# PR9024.net
KiCad netlist of a schematic drawn in EAGLE
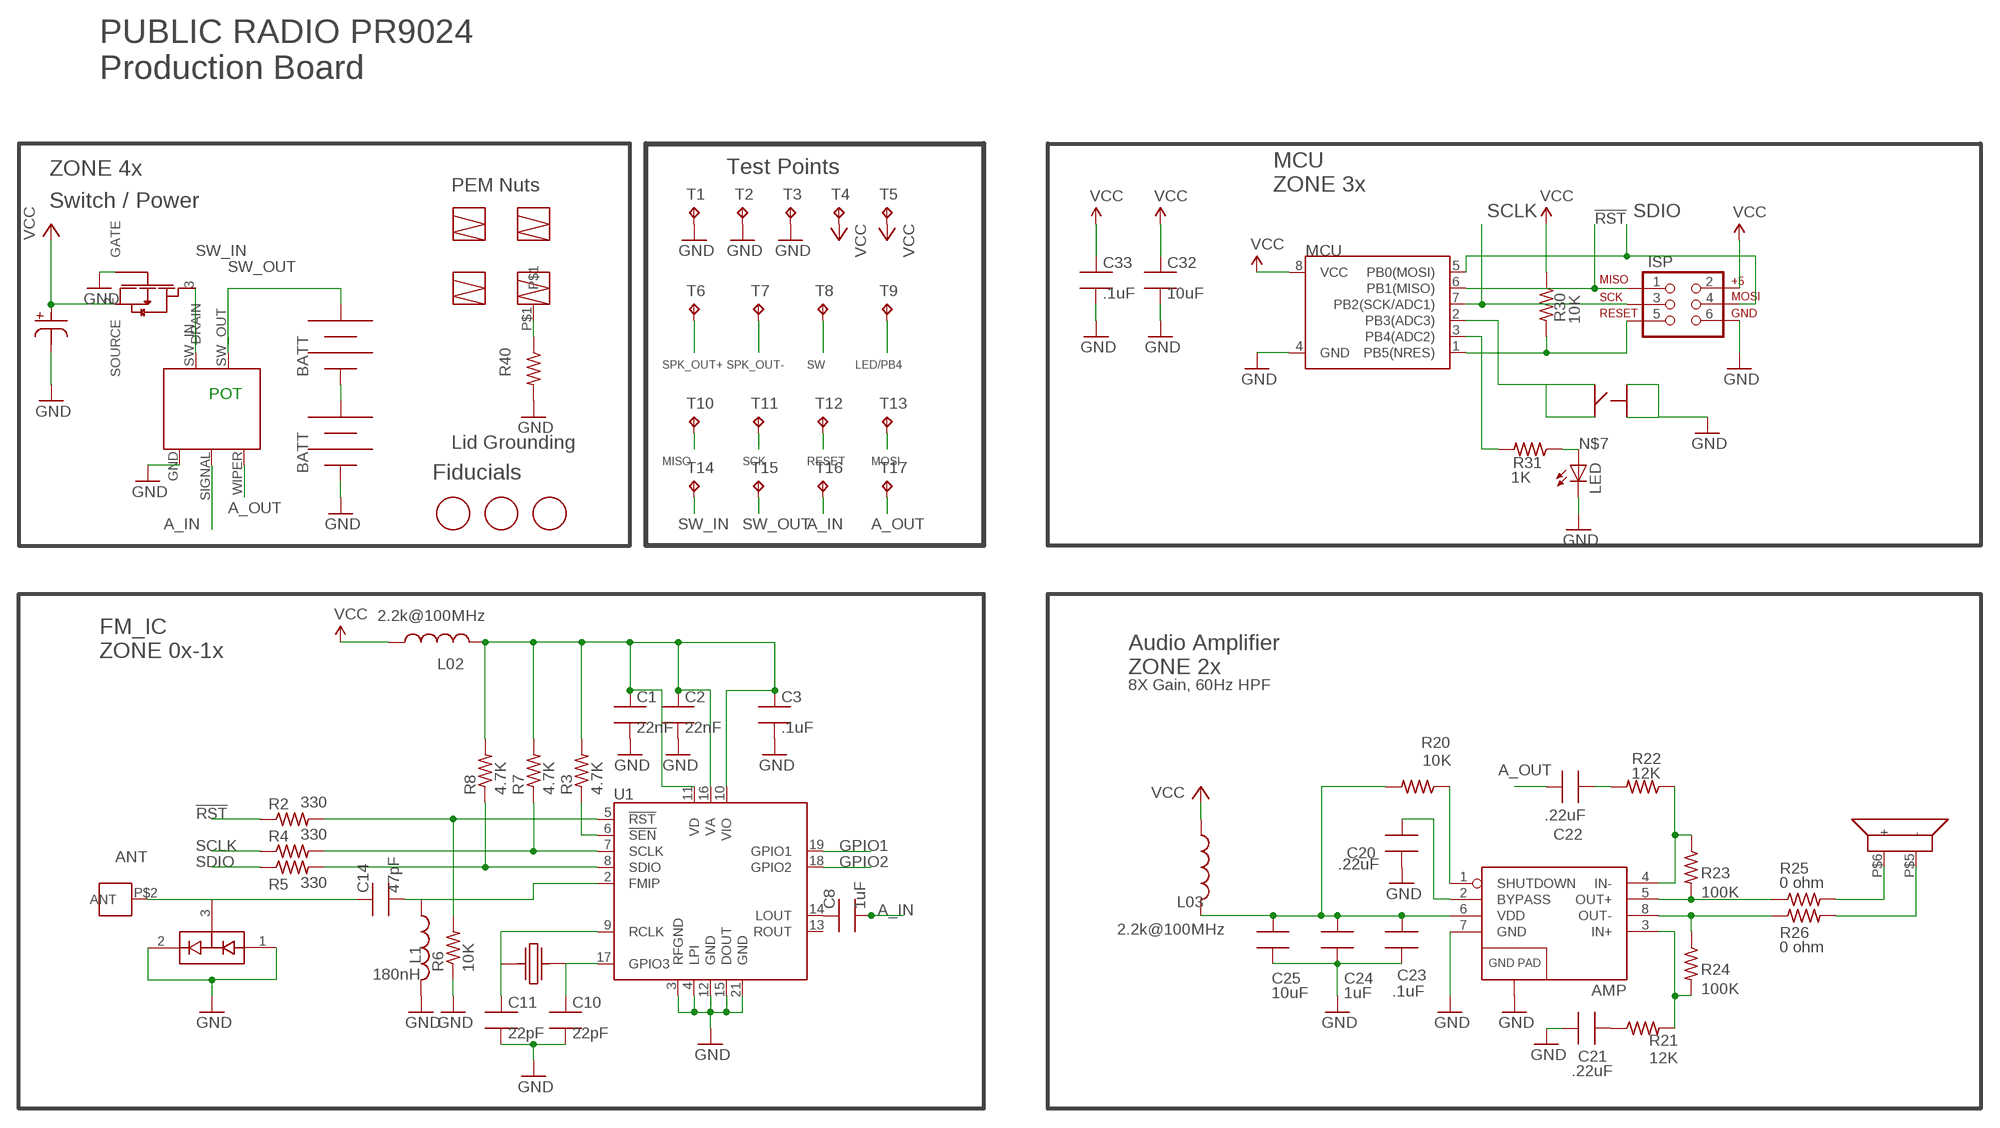
[diagram p0: schematic, sheet 1]

(export (version "E")
  (design (tool "Eeschema 10.0.6"))
  (components
    (comp (ref "AMP")
      (value "TPA6203A1")
      (footprint "eagle-import:8-MSOP")
      (libsource (lib "eagle-import") (part "TPA6203A1"))
    )
    (comp (ref "ANT_MOUNT")
      (value "DNP")
      (footprint "eagle-import:PEM_M3")
      (libsource (lib "eagle-import") (part "M3_PEMNUT"))
    )
    (comp (ref "C1")
      (value "22nF")
      (footprint "eagle-import:0603_CPL")
      (fields
        (field (name "MFG_PN") "CL10B223KB8NNNC")
        (field (name "TOL") "10%")
        (field (name "VOLTAGE") "16V")
      )
      (libsource (lib "eagle-import") (part "C_SMT_0603_CPL"))
    )
    (comp (ref "C2")
      (value "22nF")
      (footprint "eagle-import:0603_CPL")
      (fields
        (field (name "MFG_PN") "CL10B223KB8NNNC")
        (field (name "TOL") "10%")
        (field (name "VOLTAGE") "16V")
      )
      (libsource (lib "eagle-import") (part "C_SMT_0603_CPL"))
    )
    (comp (ref "C3")
      (value ".1uF")
      (footprint "eagle-import:0603_CPL")
      (fields
        (field (name "MFG_PN") "CL10B104KB8SFNC")
        (field (name "TOL") "10%")
        (field (name "VOLTAGE") "16V")
      )
      (libsource (lib "eagle-import") (part "C_SMT_0603_CPL"))
    )
    (comp (ref "C8")
      (value "1uF")
      (footprint "eagle-import:0603_CPL")
      (fields
        (field (name "MFG_PN") "CL10B105KP8NNNC")
        (field (name "TOL") "10%")
        (field (name "VOLTAGE") "10V")
      )
      (libsource (lib "eagle-import") (part "C_SMT_0603_CPL"))
    )
    (comp (ref "C10")
      (value "22pF")
      (footprint "eagle-import:0603_CPL")
      (fields
        (field (name "MFG_PN") "C1608C0G1H220J080AA")
        (field (name "TOL") "5%")
        (field (name "VOLTAGE") "50V")
      )
      (libsource (lib "eagle-import") (part "C_SMT_0603_CPL"))
    )
    (comp (ref "C11")
      (value "22pF")
      (footprint "eagle-import:0603_CPL")
      (fields
        (field (name "MFG_PN") "C1608C0G1H220J080AA")
        (field (name "TOL") "5%")
        (field (name "VOLTAGE") "50V")
      )
      (libsource (lib "eagle-import") (part "C_SMT_0603_CPL"))
    )
    (comp (ref "C14")
      (value "47pF")
      (footprint "eagle-import:0603_CPL")
      (fields
        (field (name "MFG_PN") "CL10C470JB8NCNC")
        (field (name "TOL") "5%")
        (field (name "VOLTAGE") "50V")
      )
      (libsource (lib "eagle-import") (part "C_SMT_0603_CPL"))
    )
    (comp (ref "C20")
      (value ".22uF")
      (footprint "eagle-import:0603_CPL")
      (fields
        (field (name "MFG_PN") "C1608X7R1C224K080AC")
        (field (name "TOL") "10%")
        (field (name "VOLTAGE") "16V")
      )
      (libsource (lib "eagle-import") (part "C_SMT_0603_CPL"))
    )
    (comp (ref "C21")
      (value ".22uF")
      (footprint "eagle-import:0603_CPL")
      (fields
        (field (name "MFG_PN") "C1608X7R1C224K080AC")
        (field (name "TOL") "10%")
        (field (name "VOLTAGE") "16V")
      )
      (libsource (lib "eagle-import") (part "C_SMT_0603_CPL"))
    )
    (comp (ref "C22")
      (value ".22uF")
      (footprint "eagle-import:0603_CPL")
      (fields
        (field (name "MFG_PN") "C1608X7R1C224K080AC")
        (field (name "TOL") "10%")
        (field (name "VOLTAGE") "16V")
      )
      (libsource (lib "eagle-import") (part "C_SMT_0603_CPL"))
    )
    (comp (ref "C23")
      (value ".1uF")
      (footprint "eagle-import:0603_CPL")
      (fields
        (field (name "MFG_PN") "CL10B104KB8SFNC")
        (field (name "TOL") "10%")
        (field (name "VOLTAGE") "16V")
      )
      (libsource (lib "eagle-import") (part "C_SMT_0603_CPL"))
    )
    (comp (ref "C24")
      (value "1uF")
      (footprint "eagle-import:0603_CPL")
      (fields
        (field (name "MFG_PN") "CL10B105KP8NNNC")
        (field (name "TOL") "10%")
        (field (name "VOLTAGE") "10V")
      )
      (libsource (lib "eagle-import") (part "C_SMT_0603_CPL"))
    )
    (comp (ref "C25")
      (value "10uF")
      (footprint "eagle-import:0603_CPL")
      (fields
        (field (name "MFG_PN") "CL10A106MQ8NNNC")
        (field (name "TOL") "20%")
        (field (name "VOLTAGE") "6.3V")
      )
      (libsource (lib "eagle-import") (part "C_SMT_0603_CPL"))
    )
    (comp (ref "C32")
      (value "10uF")
      (footprint "eagle-import:0603_CPL")
      (fields
        (field (name "MFG_PN") "CL10A106MQ8NNNC")
        (field (name "TOL") "20%")
        (field (name "VOLTAGE") "6.3V")
      )
      (libsource (lib "eagle-import") (part "C_SMT_0603_CPL"))
    )
    (comp (ref "C33")
      (value ".1uF")
      (footprint "eagle-import:0603_CPL")
      (fields
        (field (name "MFG_PN") "CL10B104KB8SFNC")
        (field (name "TOL") "10%")
        (field (name "VOLTAGE") "16V")
      )
      (libsource (lib "eagle-import") (part "C_SMT_0603_CPL"))
    )
    (comp (ref "C40")
      (value "220uF")
      (footprint "eagle-import:NICHICON_UD_63")
      (fields (field (name "TOL") "20%") (field (name "VOLTAGE") "16V"))
      (libsource (lib "eagle-import") (part "NICHICON_SERIESUD"))
    )
    (comp (ref "D1")
      (value "BAV99")
      (footprint "eagle-import:SOT23_CPL")
      (fields (field (name "MFG_PN") "BAV99,215"))
      (libsource (lib "eagle-import") (part "BAV99"))
    )
    (comp (ref "FET1")
      (value "AO3435")
      (footprint "eagle-import:SOT23_CPL")
      (fields (field (name "MFG_PN") "AO3435"))
      (libsource (lib "eagle-import") (part "AO3435"))
    )
    (comp (ref "ISP")
      (value "AVR_SPI_PRG_6NS")
      (footprint "eagle-import:2X3-NS")
      (libsource (lib "eagle-import") (part "AVR_SPI_PRG_6NS"))
    )
    (comp (ref "JP5")
      (value "BK-92_MPD_AA_BATT_CLIP")
      (footprint "eagle-import:BK92_AA_BATT")
      (fields (field (name "MFG_PN") "2 of BK92 - supplied by CL Labs"))
      (libsource (lib "eagle-import") (part "BK-92_MPD_AA_BATT_CLIP"))
    )
    (comp (ref "JP6")
      (value "BK-92_MPD_AA_BATT_CLIP")
      (footprint "eagle-import:BK92_AA_BATT")
      (fields (field (name "MFG_PN") "2 of BK92 - supplied by CL Labs"))
      (libsource (lib "eagle-import") (part "BK-92_MPD_AA_BATT_CLIP"))
    )
    (comp (ref "L1")
      (value "180nH")
      (footprint "eagle-import:0805_ADAFRUIT")
      (fields
        (field (name "CURRENT") "400mA")
        (field (name "DCR") "640m")
        (field (name "MFG_PN") "AISC-0805-R18J-T")
        (field (name "TOL") "5%")
      )
      (libsource (lib "eagle-import") (part "L_SMT_0805_ADAFRUIT"))
    )
    (comp (ref "L02")
      (value "2.2k@100MHz")
      (footprint "eagle-import:0603_CPL")
      (fields
        (field (name "CURRENT") "150mA")
        (field (name "DCR") "2.3")
        (field (name "MFG_PN") "HZ0603A222R-10")
      )
      (libsource (lib "eagle-import") (part "L_SMT_0603_CPL"))
    )
    (comp (ref "L03")
      (value "2.2k@100MHz")
      (footprint "eagle-import:0603_CPL")
      (fields
        (field (name "CURRENT") "150mA")
        (field (name "DCR") "2.3")
        (field (name "MFG_PN") "HZ0603A222R-10")
      )
      (libsource (lib "eagle-import") (part "L_SMT_0603_CPL"))
    )
    (comp (ref "LED")
      (value "LEDCHIPLED_0805")
      (footprint "eagle-import:CHIPLED_0805")
      (libsource (lib "eagle-import") (part "LEDCHIPLED_0805"))
    )
    (comp (ref "MARK1")
      (value "FIDUCIAL")
      (footprint "eagle-import:FIDUCIAL_1MM")
      (libsource (lib "eagle-import") (part "FIDUCIAL"))
    )
    (comp (ref "MARK2")
      (value "FIDUCIAL")
      (footprint "eagle-import:FIDUCIAL_1MM")
      (libsource (lib "eagle-import") (part "FIDUCIAL"))
    )
    (comp (ref "MARK3")
      (value "FIDUCIAL")
      (footprint "eagle-import:FIDUCIAL_1MM")
      (libsource (lib "eagle-import") (part "FIDUCIAL"))
    )
    (comp (ref "MCU")
      (value "ATTINY45TINY45-20-SMT")
      (footprint "eagle-import:8-SOIC")
      (libsource (lib "eagle-import") (part "ATTINY45TINY45-20-SMT"))
    )
    (comp (ref "R1")
      (value "VOLUME_POT")
      (footprint "eagle-import:H17112NS_A10K_L20F-002")
      (libsource (lib "eagle-import") (part "VOLUME_POT"))
    )
    (comp (ref "R2")
      (value "330")
      (footprint "eagle-import:0603_CPL")
      (fields (field (name "MFG_PN") "MCR03ERTJ331") (field (name "POWER") "1/10W") (field (name "TOL") "5%"))
      (libsource (lib "eagle-import") (part "R_SMT_R0603_CPL"))
    )
    (comp (ref "R3")
      (value "4.7K")
      (footprint "eagle-import:0603_CPL")
      (fields
        (field (name "MFG_PN") "ERJ-3EKF4701V")
        (field (name "POWER") "1/10W")
        (field (name "TOL") "1%")
      )
      (libsource (lib "eagle-import") (part "R_SMT_R0603_CPL"))
    )
    (comp (ref "R4")
      (value "330")
      (footprint "eagle-import:0603_CPL")
      (fields (field (name "MFG_PN") "MCR03ERTJ331") (field (name "POWER") "1/10W") (field (name "TOL") "5%"))
      (libsource (lib "eagle-import") (part "R_SMT_R0603_CPL"))
    )
    (comp (ref "R5")
      (value "330")
      (footprint "eagle-import:0603_CPL")
      (fields (field (name "MFG_PN") "MCR03ERTJ331") (field (name "POWER") "1/10W") (field (name "TOL") "5%"))
      (libsource (lib "eagle-import") (part "R_SMT_R0603_CPL"))
    )
    (comp (ref "R6")
      (value "10K")
      (footprint "eagle-import:0603_CPL")
      (fields
        (field (name "MFG_PN") "ERJ-3GEYJ103V")
        (field (name "POWER") "1/10W")
        (field (name "TOL") "5%")
      )
      (libsource (lib "eagle-import") (part "R_SMT_R0603_CPL"))
    )
    (comp (ref "R7")
      (value "4.7K")
      (footprint "eagle-import:0603_CPL")
      (fields
        (field (name "MFG_PN") "ERJ-3EKF4701V")
        (field (name "POWER") "1/10W")
        (field (name "TOL") "1%")
      )
      (libsource (lib "eagle-import") (part "R_SMT_R0603_CPL"))
    )
    (comp (ref "R8")
      (value "4.7K")
      (footprint "eagle-import:0603_CPL")
      (fields
        (field (name "MFG_PN") "ERJ-3EKF4701V")
        (field (name "POWER") "1/10W")
        (field (name "TOL") "1%")
      )
      (libsource (lib "eagle-import") (part "R_SMT_R0603_CPL"))
    )
    (comp (ref "R20")
      (value "10K")
      (footprint "eagle-import:0603_CPL")
      (fields
        (field (name "MFG_PN") "ERJ-3GEYJ103V")
        (field (name "POWER") "1/10W")
        (field (name "TOL") "5%")
      )
      (libsource (lib "eagle-import") (part "R_SMT_R0603_CPL"))
    )
    (comp (ref "R21")
      (value "12K")
      (footprint "eagle-import:0603_CPL")
      (fields
        (field (name "MFG_PN") "RC0603FR-0712KL")
        (field (name "POWER") "1/10W")
        (field (name "TOL") "1%")
      )
      (libsource (lib "eagle-import") (part "R_SMT_R0603_CPL"))
    )
    (comp (ref "R22")
      (value "12K")
      (footprint "eagle-import:0603_CPL")
      (fields
        (field (name "MFG_PN") "RC0603FR-0712KL")
        (field (name "POWER") "1/10W")
        (field (name "TOL") "1%")
      )
      (libsource (lib "eagle-import") (part "R_SMT_R0603_CPL"))
    )
    (comp (ref "R23")
      (value "100K")
      (footprint "eagle-import:0603_CPL")
      (fields
        (field (name "MFG_PN") "ERJ-3EKF1003V")
        (field (name "POWER") "1/10W")
        (field (name "TOL") "1%")
      )
      (libsource (lib "eagle-import") (part "R_SMT_R0603_CPL"))
    )
    (comp (ref "R24")
      (value "100K")
      (footprint "eagle-import:0603_CPL")
      (fields
        (field (name "MFG_PN") "ERJ-3EKF1003V")
        (field (name "POWER") "1/10W")
        (field (name "TOL") "1%")
      )
      (libsource (lib "eagle-import") (part "R_SMT_R0603_CPL"))
    )
    (comp (ref "R25")
      (value "0 ohm")
      (footprint "eagle-import:0805_ADAFRUIT")
      (fields (field (name "MFG_PN") "ERJ-6GEY0R00V "))
      (libsource (lib "eagle-import") (part "R_SMT_0805_ADAFRUIT"))
    )
    (comp (ref "R26")
      (value "0 ohm")
      (footprint "eagle-import:0805_ADAFRUIT")
      (fields (field (name "MFG_PN") "ERJ-6GEY0R00V "))
      (libsource (lib "eagle-import") (part "R_SMT_0805_ADAFRUIT"))
    )
    (comp (ref "R30")
      (value "10K")
      (footprint "eagle-import:0603_CPL")
      (fields
        (field (name "MFG_PN") "ERJ-3GEYJ103V")
        (field (name "POWER") "1/10W")
        (field (name "TOL") "5%")
      )
      (libsource (lib "eagle-import") (part "R_SMT_R0603_CPL"))
    )
    (comp (ref "R31")
      (value "1K")
      (footprint "eagle-import:0603_CPL")
      (fields
        (field (name "MFG_PN") "ERJ-3EKF1001V")
        (field (name "POWER") "1/10W")
        (field (name "TOL") "1%")
      )
      (libsource (lib "eagle-import") (part "R_SMT_R0603_CPL"))
    )
    (comp (ref "R40")
      (value "DNP")
      (footprint "eagle-import:0603_CPL")
      (fields (field (name "MFG_PN") "ERJ-3GEY0R00V"))
      (libsource (lib "eagle-import") (part "R_SMT_R0603_CPL"))
    )
    (comp (ref "SPKR_PLACE")
      (value "DNP")
      (footprint "eagle-import:PR2024_SPKR_PLACE(SMD)")
      (libsource (lib "eagle-import") (part "PR2024_SPKR_SMD"))
    )
    (comp (ref "SW1")
      (value "C&K_PTS645")
      (footprint "eagle-import:C&K_PTS645_SMT")
      (libsource (lib "eagle-import") (part "C&K_PTS645"))
    )
    (comp (ref "T1")
      (value "TPTP20R")
      (footprint "eagle-import:TP20R")
      (libsource (lib "eagle-import") (part "TPTP20R"))
    )
    (comp (ref "T2")
      (value "TPTP20R")
      (footprint "eagle-import:TP20R")
      (libsource (lib "eagle-import") (part "TPTP20R"))
    )
    (comp (ref "T3")
      (value "TPTP20R")
      (footprint "eagle-import:TP20R")
      (libsource (lib "eagle-import") (part "TPTP20R"))
    )
    (comp (ref "T4")
      (value "TPTP20R")
      (footprint "eagle-import:TP20R")
      (libsource (lib "eagle-import") (part "TPTP20R"))
    )
    (comp (ref "T5")
      (value "TPTP20R")
      (footprint "eagle-import:TP20R")
      (libsource (lib "eagle-import") (part "TPTP20R"))
    )
    (comp (ref "T6")
      (value "TPTP20R")
      (footprint "eagle-import:TP20R")
      (libsource (lib "eagle-import") (part "TPTP20R"))
    )
    (comp (ref "T7")
      (value "TPTP20R")
      (footprint "eagle-import:TP20R")
      (libsource (lib "eagle-import") (part "TPTP20R"))
    )
    (comp (ref "T8")
      (value "TPTP20R")
      (footprint "eagle-import:TP20R")
      (libsource (lib "eagle-import") (part "TPTP20R"))
    )
    (comp (ref "T9")
      (value "TPTP20R")
      (footprint "eagle-import:TP20R")
      (libsource (lib "eagle-import") (part "TPTP20R"))
    )
    (comp (ref "T10")
      (value "TPTP20R")
      (footprint "eagle-import:TP20R")
      (libsource (lib "eagle-import") (part "TPTP20R"))
    )
    (comp (ref "T11")
      (value "TPTP20R")
      (footprint "eagle-import:TP20R")
      (libsource (lib "eagle-import") (part "TPTP20R"))
    )
    (comp (ref "T12")
      (value "TPTP20R")
      (footprint "eagle-import:TP20R")
      (libsource (lib "eagle-import") (part "TPTP20R"))
    )
    (comp (ref "T13")
      (value "TPTP20R")
      (footprint "eagle-import:TP20R")
      (libsource (lib "eagle-import") (part "TPTP20R"))
    )
    (comp (ref "T14")
      (value "TPTP20R")
      (footprint "eagle-import:TP20R")
      (libsource (lib "eagle-import") (part "TPTP20R"))
    )
    (comp (ref "T15")
      (value "TPTP20R")
      (footprint "eagle-import:TP20R")
      (libsource (lib "eagle-import") (part "TPTP20R"))
    )
    (comp (ref "T16")
      (value "TPTP20R")
      (footprint "eagle-import:TP20R")
      (libsource (lib "eagle-import") (part "TPTP20R"))
    )
    (comp (ref "T17")
      (value "TPTP20R")
      (footprint "eagle-import:TP20R")
      (libsource (lib "eagle-import") (part "TPTP20R"))
    )
    (comp (ref "U$2")
      (value "PEM_SMT")
      (footprint "eagle-import:PEM_SMT")
      (libsource (lib "eagle-import") (part "PEM_SMT"))
    )
    (comp (ref "U$3")
      (value "PEM_SMT")
      (footprint "eagle-import:PEM_SMT")
      (libsource (lib "eagle-import") (part "PEM_SMT"))
    )
    (comp (ref "U$4")
      (value "PEM_SMT")
      (footprint "eagle-import:PEM_SMT")
      (libsource (lib "eagle-import") (part "PEM_SMT"))
    )
    (comp (ref "U$5")
      (value "PEM_M3_SMT_W/PIN")
      (footprint "eagle-import:PEM_SMT")
      (libsource (lib "eagle-import") (part "PEM_M3_SMT_W/PIN"))
    )
    (comp (ref "U1")
      (value "SI4702-C19-GMR")
      (footprint "eagle-import:SI470X_20_QFN")
      (fields (field (name "MFG_PN") "Si4702 C19 GM - supplied by CL Labs"))
      (libsource (lib "eagle-import") (part "SI4702-C19-GMR"))
    )
    (comp (ref "X1")
      (value "ABS25XTAL")
      (footprint "eagle-import:4-SOJ")
      (libsource (lib "eagle-import") (part "ABS25XTAL"))
    )
  )
  (nets
    (net (code "1") (name "/ANT") (class "Default")
      (node (ref "ANT_MOUNT") (pin "P$2") (pinfunction "ANT_P$2") (pintype "bidirectional"))
      (node (ref "C14") (pin "1") (pinfunction "1_1") (pintype "passive"))
      (node (ref "D1") (pin "3") (pinfunction "COM_3") (pintype "bidirectional"))
    )
    (net (code "2") (name "/A_IN") (class "Default")
      (node (ref "C8") (pin "2") (pinfunction "2_2") (pintype "passive"))
      (node (ref "R1") (pin "SIGNAL") (pinfunction "SIGNAL_SIGNAL") (pintype "bidirectional"))
      (node (ref "T16") (pin "TP") (pinfunction "TP_TP") (pintype "input"))
    )
    (net (code "3") (name "/A_OUT") (class "Default")
      (node (ref "C22") (pin "2") (pinfunction "2_2") (pintype "passive"))
      (node (ref "R1") (pin "WIPER") (pinfunction "WIPER_WIPER") (pintype "bidirectional"))
      (node (ref "T17") (pin "TP") (pinfunction "TP_TP") (pintype "input"))
    )
    (net (code "4") (name "/GPIO1") (class "Default")
      (node (ref "U1") (pin "19") (pinfunction "GPIO1_19") (pintype "bidirectional"))
    )
    (net (code "5") (name "/GPIO2") (class "Default")
      (node (ref "U1") (pin "18") (pinfunction "GPIO2_18") (pintype "bidirectional"))
    )
    (net (code "6") (name "/LED{slash}PB4") (class "Default")
      (node (ref "MCU") (pin "3") (pinfunction "PB4(ADC2)_3") (pintype "bidirectional"))
      (node (ref "R31") (pin "2") (pinfunction "2_2") (pintype "passive"))
      (node (ref "T9") (pin "TP") (pinfunction "TP_TP") (pintype "input"))
    )
    (net (code "7") (name "/N$7") (class "Default")
      (node (ref "LED") (pin "A") (pinfunction "A_A") (pintype "passive"))
      (node (ref "R31") (pin "1") (pinfunction "1_1") (pintype "passive"))
    )
    (net (code "8") (name "/RESET") (class "Default")
      (node (ref "ISP") (pin "5") (pinfunction "5_5") (pintype "passive"))
      (node (ref "MCU") (pin "1") (pinfunction "PB5(NRES)_1") (pintype "bidirectional"))
      (node (ref "R30") (pin "2") (pinfunction "2_2") (pintype "passive"))
      (node (ref "T12") (pin "TP") (pinfunction "TP_TP") (pintype "input"))
    )
    (net (code "9") (name "/SCLK") (class "Default")
      (node (ref "ISP") (pin "3") (pinfunction "3_3") (pintype "passive"))
      (node (ref "MCU") (pin "7") (pinfunction "PB2(SCK/ADC1)_7") (pintype "bidirectional"))
      (node (ref "R4") (pin "1") (pinfunction "1_1") (pintype "passive"))
      (node (ref "T11") (pin "TP") (pinfunction "TP_TP") (pintype "input"))
    )
    (net (code "10") (name "/SDIO") (class "Default")
      (node (ref "ISP") (pin "4") (pinfunction "4_4") (pintype "passive"))
      (node (ref "MCU") (pin "5") (pinfunction "PB0(MOSI)_5") (pintype "bidirectional"))
      (node (ref "R5") (pin "1") (pinfunction "1_1") (pintype "passive"))
      (node (ref "T13") (pin "TP") (pinfunction "TP_TP") (pintype "input"))
    )
    (net (code "11") (name "/SPK_OUT+") (class "Default")
      (node (ref "R25") (pin "2") (pinfunction "2_2") (pintype "passive"))
      (node (ref "SPKR_PLACE") (pin "P$6") (pinfunction "+_P$6") (pintype "bidirectional"))
      (node (ref "T6") (pin "TP") (pinfunction "TP_TP") (pintype "input"))
    )
    (net (code "12") (name "/SPK_OUT-") (class "Default")
      (node (ref "R26") (pin "2") (pinfunction "2_2") (pintype "passive"))
      (node (ref "SPKR_PLACE") (pin "P$5") (pinfunction "-_P$5") (pintype "bidirectional"))
      (node (ref "T7") (pin "TP") (pinfunction "TP_TP") (pintype "input"))
    )
    (net (code "13") (name "/SW") (class "Default")
      (node (ref "MCU") (pin "2") (pinfunction "PB3(ADC3)_2") (pintype "bidirectional"))
      (node (ref "SW1") (pin "P$3") (pinfunction "P$3_P$3") (pintype "bidirectional"))
      (node (ref "SW1") (pin "P$4") (pinfunction "P$4_P$4") (pintype "bidirectional"))
      (node (ref "T8") (pin "TP") (pinfunction "TP_TP") (pintype "input"))
    )
    (net (code "14") (name "/SW_IN") (class "Default")
      (node (ref "FET1") (pin "3") (pinfunction "DRAIN_3") (pintype "bidirectional"))
      (node (ref "R1") (pin "SW_IN") (pinfunction "SW_IN_SW_IN") (pintype "bidirectional"))
      (node (ref "T14") (pin "TP") (pinfunction "TP_TP") (pintype "input"))
    )
    (net (code "15") (name "/SW_OUT") (class "Default")
      (node (ref "JP5") (pin "POS") (pinfunction "POS_POS") (pintype "bidirectional"))
      (node (ref "JP5") (pin "POS@2") (pinfunction "POS_POS@2") (pintype "bidirectional"))
      (node (ref "R1") (pin "SW_OUT") (pinfunction "SW_OUT_SW_OUT") (pintype "bidirectional"))
      (node (ref "T15") (pin "TP") (pinfunction "TP_TP") (pintype "input"))
    )
    (net (code "16") (name "/~{RST}") (class "Default")
      (node (ref "ISP") (pin "1") (pinfunction "1_1") (pintype "passive"))
      (node (ref "MCU") (pin "6") (pinfunction "PB1(MISO)_6") (pintype "bidirectional"))
      (node (ref "R2") (pin "1") (pinfunction "1_1") (pintype "passive"))
      (node (ref "T10") (pin "TP") (pinfunction "TP_TP") (pintype "input"))
    )
    (net (code "17") (name "GND") (class "Default")
      (node (ref "AMP") (pin "7") (pinfunction "GND_7") (pintype "power_in"))
      (node (ref "AMP") (pin "9") (pinfunction "GND_9") (pintype "power_in"))
      (node (ref "C1") (pin "2") (pinfunction "2_2") (pintype "passive"))
      (node (ref "C10") (pin "2") (pinfunction "2_2") (pintype "passive"))
      (node (ref "C11") (pin "2") (pinfunction "2_2") (pintype "passive"))
      (node (ref "C2") (pin "2") (pinfunction "2_2") (pintype "passive"))
      (node (ref "C20") (pin "1") (pinfunction "1_1") (pintype "passive"))
      (node (ref "C21") (pin "1") (pinfunction "1_1") (pintype "passive"))
      (node (ref "C23") (pin "2") (pinfunction "2_2") (pintype "passive"))
      (node (ref "C24") (pin "2") (pinfunction "2_2") (pintype "passive"))
      (node (ref "C25") (pin "2") (pinfunction "2_2") (pintype "passive"))
      (node (ref "C3") (pin "2") (pinfunction "2_2") (pintype "passive"))
      (node (ref "C32") (pin "2") (pinfunction "2_2") (pintype "passive"))
      (node (ref "C33") (pin "2") (pinfunction "2_2") (pintype "passive"))
      (node (ref "C40") (pin "P$2") (pinfunction "P$2_P$2") (pintype "bidirectional"))
      (node (ref "D1") (pin "1") (pinfunction "A1_1") (pintype "bidirectional"))
      (node (ref "D1") (pin "2") (pinfunction "C2_2") (pintype "bidirectional"))
      (node (ref "FET1") (pin "1") (pinfunction "GATE_1") (pintype "bidirectional"))
      (node (ref "ISP") (pin "6") (pinfunction "6_6") (pintype "passive"))
      (node (ref "JP6") (pin "NEG") (pinfunction "NEG_NEG") (pintype "bidirectional"))
      (node (ref "JP6") (pin "NEG@2") (pinfunction "NEG_NEG@2") (pintype "bidirectional"))
      (node (ref "L1") (pin "2") (pinfunction "2_2") (pintype "passive"))
      (node (ref "LED") (pin "C") (pinfunction "C_C") (pintype "passive"))
      (node (ref "MCU") (pin "4") (pinfunction "GND_4") (pintype "bidirectional"))
      (node (ref "R1") (pin "GND") (pinfunction "GND_GND") (pintype "bidirectional"))
      (node (ref "R40") (pin "2") (pinfunction "2_2") (pintype "passive"))
      (node (ref "R6") (pin "1") (pinfunction "1_1") (pintype "passive"))
      (node (ref "SW1") (pin "P$1") (pinfunction "P$1_P$1") (pintype "bidirectional"))
      (node (ref "SW1") (pin "P$2") (pinfunction "P$2_P$2") (pintype "bidirectional"))
      (node (ref "T1") (pin "TP") (pinfunction "TP_TP") (pintype "input"))
      (node (ref "T2") (pin "TP") (pinfunction "TP_TP") (pintype "input"))
      (node (ref "T3") (pin "TP") (pinfunction "TP_TP") (pintype "input"))
      (node (ref "U1") (pin "12") (pinfunction "GND_12") (pintype "bidirectional"))
      (node (ref "U1") (pin "15") (pinfunction "DOUT_15") (pintype "bidirectional"))
      (node (ref "U1") (pin "21") (pinfunction "GND_21") (pintype "bidirectional"))
      (node (ref "U1") (pin "3") (pinfunction "RFGND_3") (pintype "bidirectional"))
      (node (ref "U1") (pin "4") (pinfunction "LPI_4") (pintype "bidirectional"))
    )
    (net (code "18") (name "Net-(AMP-BYPASS)") (class "Default")
      (node (ref "AMP") (pin "2") (pinfunction "BYPASS_2") (pintype "bidirectional"))
      (node (ref "C20") (pin "2") (pinfunction "2_2") (pintype "passive"))
    )
    (net (code "19") (name "Net-(AMP-IN+)") (class "Default")
      (node (ref "AMP") (pin "3") (pinfunction "IN+_3") (pintype "bidirectional"))
      (node (ref "R21") (pin "2") (pinfunction "2_2") (pintype "passive"))
      (node (ref "R24") (pin "2") (pinfunction "2_2") (pintype "passive"))
    )
    (net (code "20") (name "Net-(AMP-IN-)") (class "Default")
      (node (ref "AMP") (pin "4") (pinfunction "IN-_4") (pintype "bidirectional"))
      (node (ref "R22") (pin "1") (pinfunction "1_1") (pintype "passive"))
      (node (ref "R23") (pin "1") (pinfunction "1_1") (pintype "passive"))
    )
    (net (code "21") (name "Net-(AMP-OUT+)") (class "Default")
      (node (ref "AMP") (pin "5") (pinfunction "OUT+_5") (pintype "bidirectional"))
      (node (ref "R23") (pin "2") (pinfunction "2_2") (pintype "passive"))
      (node (ref "R25") (pin "1") (pinfunction "1_1") (pintype "passive"))
    )
    (net (code "22") (name "Net-(AMP-OUT-)") (class "Default")
      (node (ref "AMP") (pin "8") (pinfunction "OUT-_8") (pintype "bidirectional"))
      (node (ref "R24") (pin "1") (pinfunction "1_1") (pintype "passive"))
      (node (ref "R26") (pin "1") (pinfunction "1_1") (pintype "passive"))
    )
    (net (code "23") (name "Net-(AMP-SHUTDOWN)") (class "Default")
      (node (ref "AMP") (pin "1") (pinfunction "SHUTDOWN_1") (pintype "input"))
      (node (ref "R20") (pin "1") (pinfunction "1_1") (pintype "passive"))
    )
    (net (code "24") (name "Net-(AMP-VDD)") (class "Default")
      (node (ref "AMP") (pin "6") (pinfunction "VDD_6") (pintype "power_in"))
      (node (ref "C23") (pin "1") (pinfunction "1_1") (pintype "passive"))
      (node (ref "C24") (pin "1") (pinfunction "1_1") (pintype "passive"))
      (node (ref "C25") (pin "1") (pinfunction "1_1") (pintype "passive"))
      (node (ref "L03") (pin "2") (pinfunction "2_2") (pintype "passive"))
      (node (ref "R20") (pin "2") (pinfunction "2_2") (pintype "passive"))
    )
    (net (code "25") (name "Net-(C21-Pad2)") (class "Default")
      (node (ref "C21") (pin "2") (pinfunction "2_2") (pintype "passive"))
      (node (ref "R21") (pin "1") (pinfunction "1_1") (pintype "passive"))
    )
    (net (code "26") (name "Net-(C22-Pad1)") (class "Default")
      (node (ref "C22") (pin "1") (pinfunction "1_1") (pintype "passive"))
      (node (ref "R22") (pin "2") (pinfunction "2_2") (pintype "passive"))
    )
    (net (code "27") (name "Net-(JP5-NEG-PadNEG@2)") (class "Default")
      (node (ref "JP5") (pin "NEG") (pinfunction "NEG_NEG") (pintype "bidirectional"))
      (node (ref "JP5") (pin "NEG@2") (pinfunction "NEG_NEG@2") (pintype "bidirectional"))
      (node (ref "JP6") (pin "POS") (pinfunction "POS_POS") (pintype "bidirectional"))
      (node (ref "JP6") (pin "POS@2") (pinfunction "POS_POS@2") (pintype "bidirectional"))
    )
    (net (code "28") (name "Net-(R40-Pad1)") (class "Default")
      (node (ref "R40") (pin "1") (pinfunction "1_1") (pintype "passive"))
      (node (ref "U$5") (pin "P$1") (pinfunction "P$1_P$1") (pintype "bidirectional"))
    )
    (net (code "29") (name "Net-(U1-FMIP)") (class "Default")
      (node (ref "C14") (pin "2") (pinfunction "2_2") (pintype "passive"))
      (node (ref "L1") (pin "1") (pinfunction "1_1") (pintype "passive"))
      (node (ref "U1") (pin "2") (pinfunction "FMIP_2") (pintype "bidirectional"))
    )
    (net (code "30") (name "Net-(U1-GPIO3)") (class "Default")
      (node (ref "C10") (pin "1") (pinfunction "1_1") (pintype "passive"))
      (node (ref "U1") (pin "17") (pinfunction "GPIO3_17") (pintype "bidirectional"))
      (node (ref "X1") (pin "P$4") (pinfunction "P$4_P$4") (pintype "bidirectional"))
    )
    (net (code "31") (name "Net-(U1-LOUT)") (class "Default")
      (node (ref "C8") (pin "1") (pinfunction "1_1") (pintype "passive"))
      (node (ref "U1") (pin "14") (pinfunction "LOUT_14") (pintype "bidirectional"))
    )
    (net (code "32") (name "Net-(U1-RCLK)") (class "Default")
      (node (ref "C11") (pin "1") (pinfunction "1_1") (pintype "passive"))
      (node (ref "U1") (pin "9") (pinfunction "RCLK_9") (pintype "bidirectional"))
      (node (ref "X1") (pin "P$1") (pinfunction "P$1_P$1") (pintype "bidirectional"))
    )
    (net (code "33") (name "Net-(U1-SCLK)") (class "Default")
      (node (ref "R4") (pin "2") (pinfunction "2_2") (pintype "passive"))
      (node (ref "R7") (pin "1") (pinfunction "1_1") (pintype "passive"))
      (node (ref "U1") (pin "7") (pinfunction "SCLK_7") (pintype "bidirectional"))
    )
    (net (code "34") (name "Net-(U1-SDIO)") (class "Default")
      (node (ref "R5") (pin "2") (pinfunction "2_2") (pintype "passive"))
      (node (ref "R8") (pin "1") (pinfunction "1_1") (pintype "passive"))
      (node (ref "U1") (pin "8") (pinfunction "SDIO_8") (pintype "bidirectional"))
    )
    (net (code "35") (name "Net-(U1-VA)") (class "Default")
      (node (ref "C1") (pin "1") (pinfunction "1_1") (pintype "passive"))
      (node (ref "C2") (pin "1") (pinfunction "1_1") (pintype "passive"))
      (node (ref "C3") (pin "1") (pinfunction "1_1") (pintype "passive"))
      (node (ref "L02") (pin "2") (pinfunction "2_2") (pintype "passive"))
      (node (ref "R3") (pin "2") (pinfunction "2_2") (pintype "passive"))
      (node (ref "R7") (pin "2") (pinfunction "2_2") (pintype "passive"))
      (node (ref "R8") (pin "2") (pinfunction "2_2") (pintype "passive"))
      (node (ref "U1") (pin "10") (pinfunction "VIO_10") (pintype "bidirectional"))
      (node (ref "U1") (pin "11") (pinfunction "VD_11") (pintype "bidirectional"))
      (node (ref "U1") (pin "16") (pinfunction "VA_16") (pintype "bidirectional"))
    )
    (net (code "36") (name "Net-(U1-~{RST})") (class "Default")
      (node (ref "R2") (pin "2") (pinfunction "2_2") (pintype "passive"))
      (node (ref "R6") (pin "2") (pinfunction "2_2") (pintype "passive"))
      (node (ref "U1") (pin "5") (pinfunction "~{RST}_5") (pintype "bidirectional"))
    )
    (net (code "37") (name "Net-(U1-~{SEN})") (class "Default")
      (node (ref "R3") (pin "1") (pinfunction "1_1") (pintype "passive"))
      (node (ref "U1") (pin "6") (pinfunction "~{SEN}_6") (pintype "bidirectional"))
    )
    (net (code "38") (name "VCC") (class "Default")
      (node (ref "C32") (pin "1") (pinfunction "1_1") (pintype "passive"))
      (node (ref "C33") (pin "1") (pinfunction "1_1") (pintype "passive"))
      (node (ref "C40") (pin "P$1") (pinfunction "P$1_P$1") (pintype "bidirectional"))
      (node (ref "FET1") (pin "2") (pinfunction "SOURCE_2") (pintype "bidirectional"))
      (node (ref "ISP") (pin "2") (pinfunction "2_2") (pintype "passive"))
      (node (ref "L02") (pin "1") (pinfunction "1_1") (pintype "passive"))
      (node (ref "L03") (pin "1") (pinfunction "1_1") (pintype "passive"))
      (node (ref "MCU") (pin "8") (pinfunction "VCC_8") (pintype "bidirectional"))
      (node (ref "R30") (pin "1") (pinfunction "1_1") (pintype "passive"))
      (node (ref "T4") (pin "TP") (pinfunction "TP_TP") (pintype "input"))
      (node (ref "T5") (pin "TP") (pinfunction "TP_TP") (pintype "input"))
    )
    (net (code "39") (name "unconnected-(U1-ROUT-Pad13)") (class "Default")
      (node (ref "U1") (pin "13") (pinfunction "ROUT_13") (pintype "bidirectional"))
    )
  )
)
